# OwlModular.net
KiCad netlist of a schematic drawn in EAGLE
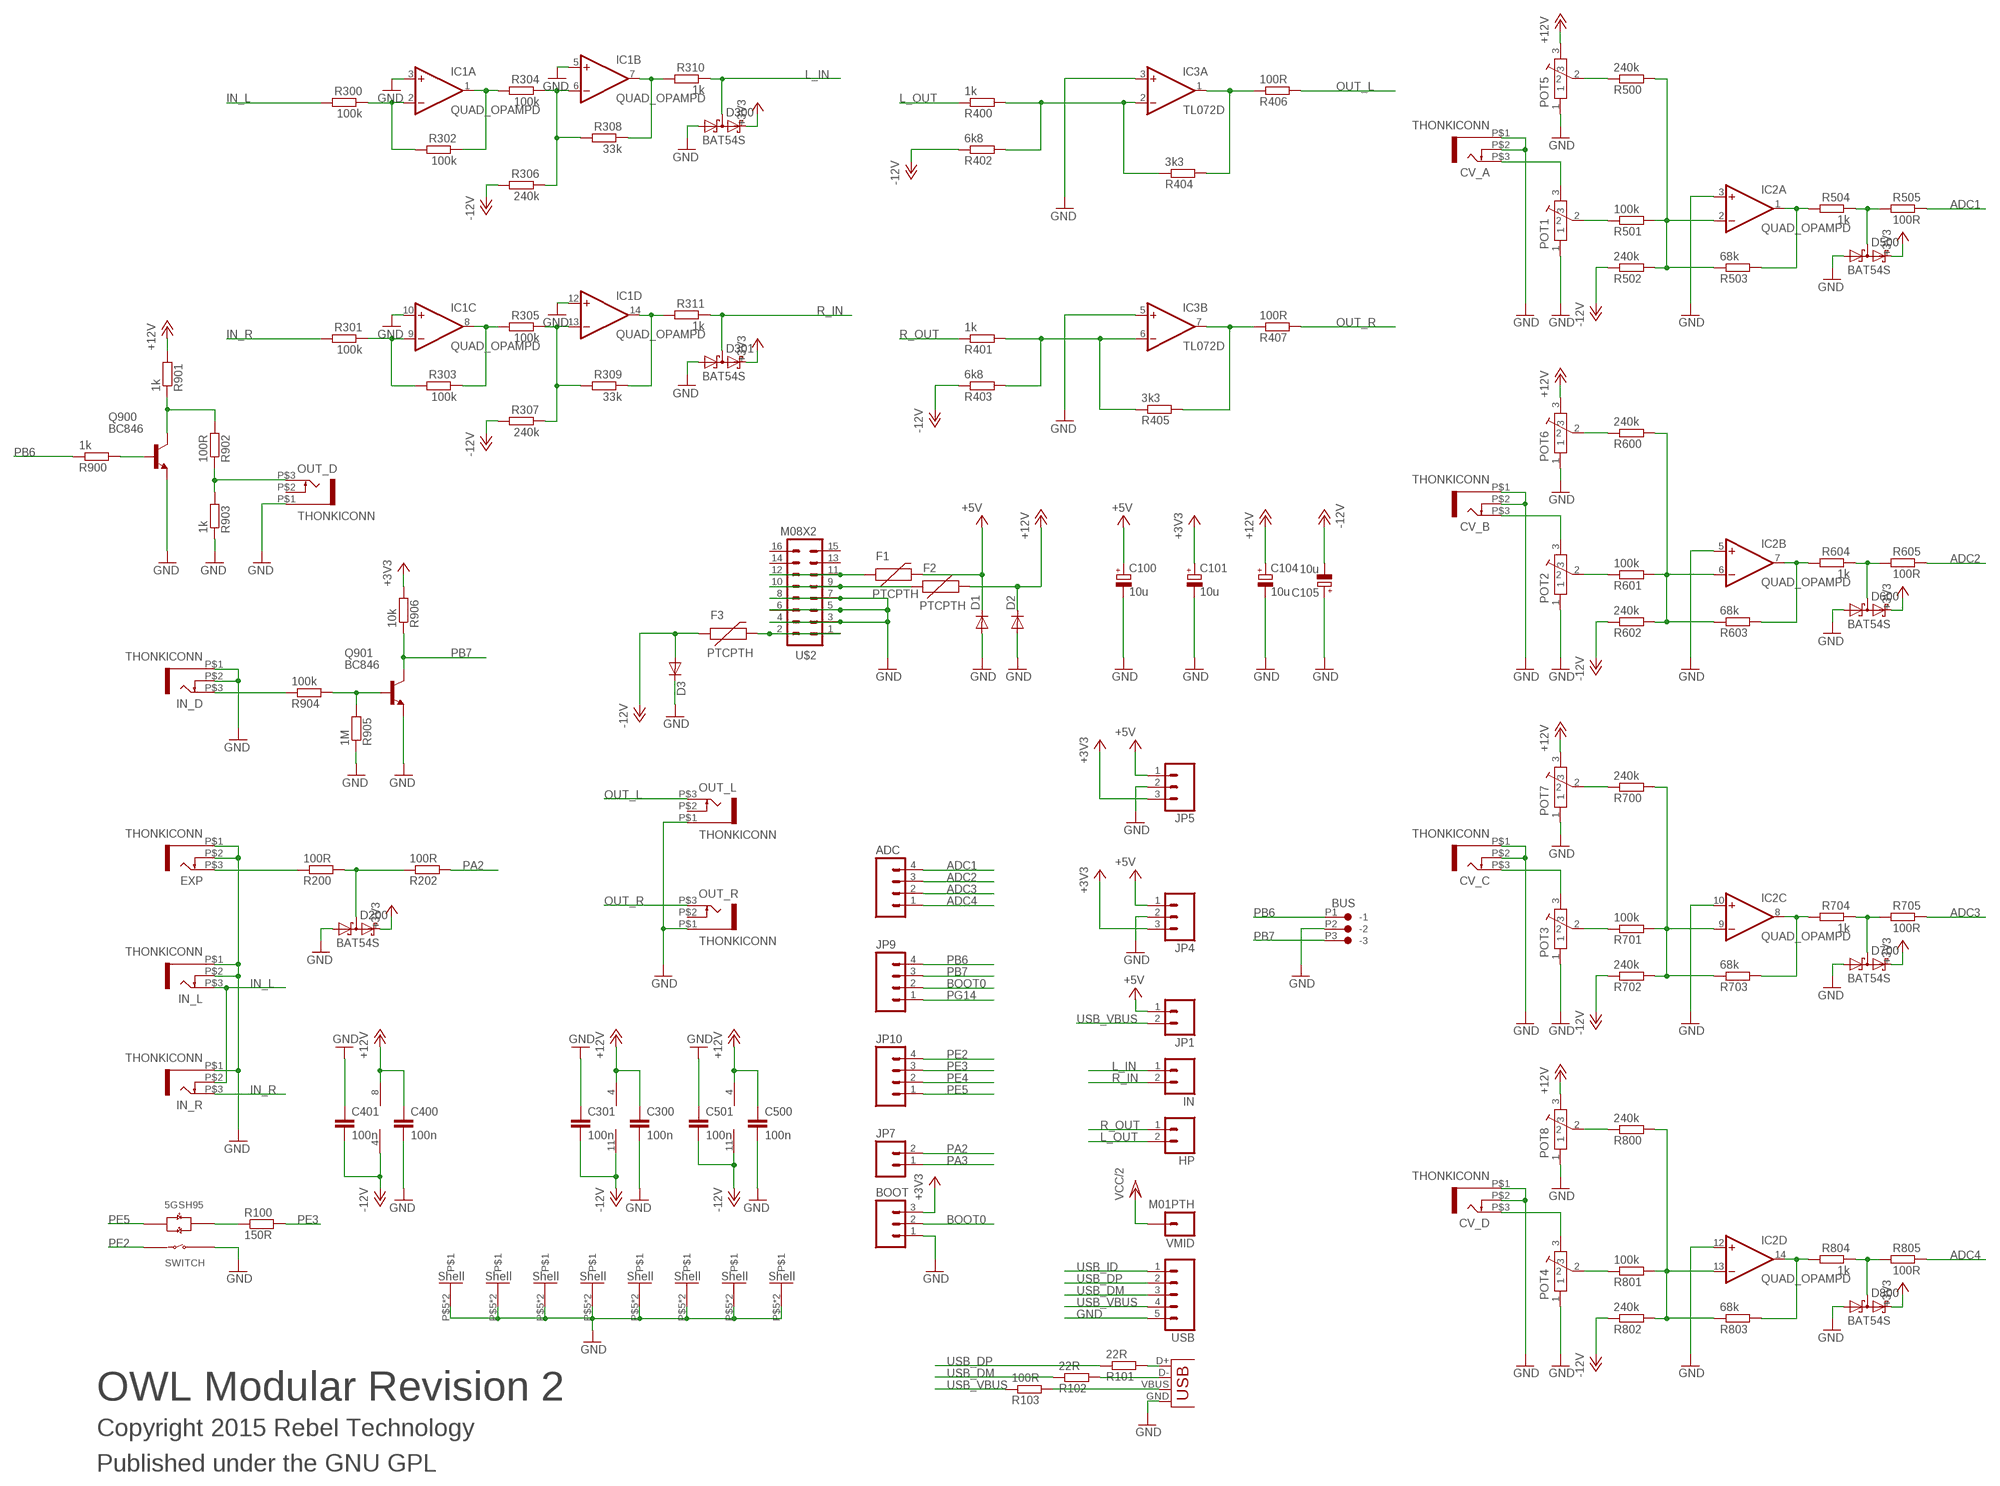
[diagram p0: schematic, sheet 1]

(export (version "E")
  (design (tool "Eeschema 10.0.6"))
  (components
    (comp (ref "ADC")
      (value "M04PTH")
      (footprint "eagle-import:1X04")
      (libsource (lib "eagle-import") (part "M04PTH"))
    )
    (comp (ref "BOOT")
      (value "M03PTH")
      (footprint "eagle-import:1X03")
      (libsource (lib "eagle-import") (part "M03PTH"))
    )
    (comp (ref "BUS")
      (value "CON-JST_PH_3W")
      (footprint "eagle-import:CON-JST_PH_3W")
      (libsource (lib "eagle-import") (part "CON-JST_PH_3W"))
    )
    (comp (ref "C100")
      (value "10u")
      (footprint "eagle-import:PANASONIC_A")
      (libsource (lib "eagle-import") (part "CPOL-EUA"))
    )
    (comp (ref "C101")
      (value "10u")
      (footprint "eagle-import:PANASONIC_A")
      (libsource (lib "eagle-import") (part "CPOL-EUA"))
    )
    (comp (ref "C104")
      (value "10u")
      (footprint "eagle-import:PANASONIC_A")
      (libsource (lib "eagle-import") (part "CPOL-EUA"))
    )
    (comp (ref "C105")
      (value "10u")
      (footprint "eagle-import:PANASONIC_A")
      (libsource (lib "eagle-import") (part "CPOL-EUA"))
    )
    (comp (ref "C300")
      (value "100n")
      (footprint "eagle-import:C0603")
      (libsource (lib "eagle-import") (part "C-EUC0603"))
    )
    (comp (ref "C301")
      (value "100n")
      (footprint "eagle-import:C0603")
      (libsource (lib "eagle-import") (part "C-EUC0603"))
    )
    (comp (ref "C400")
      (value "100n")
      (footprint "eagle-import:C0603")
      (libsource (lib "eagle-import") (part "C-EUC0603"))
    )
    (comp (ref "C401")
      (value "100n")
      (footprint "eagle-import:C0603")
      (libsource (lib "eagle-import") (part "C-EUC0603"))
    )
    (comp (ref "C500")
      (value "100n")
      (footprint "eagle-import:C0603")
      (libsource (lib "eagle-import") (part "C-EUC0603"))
    )
    (comp (ref "C501")
      (value "100n")
      (footprint "eagle-import:C0603")
      (libsource (lib "eagle-import") (part "C-EUC0603"))
    )
    (comp (ref "CV_A")
      (value "THONKICONN")
      (footprint "eagle-import:THONKICONN")
      (libsource (lib "eagle-import") (part "THONKICONN"))
    )
    (comp (ref "CV_B")
      (value "THONKICONN")
      (footprint "eagle-import:THONKICONN")
      (libsource (lib "eagle-import") (part "THONKICONN"))
    )
    (comp (ref "CV_C")
      (value "THONKICONN")
      (footprint "eagle-import:THONKICONN")
      (libsource (lib "eagle-import") (part "THONKICONN"))
    )
    (comp (ref "CV_D")
      (value "THONKICONN")
      (footprint "eagle-import:THONKICONN")
      (libsource (lib "eagle-import") (part "THONKICONN"))
    )
    (comp (ref "D1")
      (value "DIODE1N4001")
      (footprint "eagle-import:DIODE-1N4001")
      (libsource (lib "eagle-import") (part "DIODE1N4001"))
    )
    (comp (ref "D2")
      (value "DIODE1N4001")
      (footprint "eagle-import:DIODE-1N4001")
      (libsource (lib "eagle-import") (part "DIODE1N4001"))
    )
    (comp (ref "D3")
      (value "DIODE1N4001")
      (footprint "eagle-import:DIODE-1N4001")
      (libsource (lib "eagle-import") (part "DIODE1N4001"))
    )
    (comp (ref "D200")
      (value "BAT54S")
      (footprint "eagle-import:SOT23")
      (libsource (lib "eagle-import") (part "BAT54S"))
    )
    (comp (ref "D300")
      (value "BAT54S")
      (footprint "eagle-import:SOT23")
      (libsource (lib "eagle-import") (part "BAT54S"))
    )
    (comp (ref "D301")
      (value "BAT54S")
      (footprint "eagle-import:SOT23")
      (libsource (lib "eagle-import") (part "BAT54S"))
    )
    (comp (ref "D500")
      (value "BAT54S")
      (footprint "eagle-import:SOT23")
      (libsource (lib "eagle-import") (part "BAT54S"))
    )
    (comp (ref "D600")
      (value "BAT54S")
      (footprint "eagle-import:SOT23")
      (libsource (lib "eagle-import") (part "BAT54S"))
    )
    (comp (ref "D700")
      (value "BAT54S")
      (footprint "eagle-import:SOT23")
      (libsource (lib "eagle-import") (part "BAT54S"))
    )
    (comp (ref "D800")
      (value "BAT54S")
      (footprint "eagle-import:SOT23")
      (libsource (lib "eagle-import") (part "BAT54S"))
    )
    (comp (ref "EXP")
      (value "THONKICONN")
      (footprint "eagle-import:THONKICONN")
      (libsource (lib "eagle-import") (part "THONKICONN"))
    )
    (comp (ref "F1")
      (value "PTCPTH")
      (footprint "eagle-import:PTC")
      (libsource (lib "eagle-import") (part "PTCPTH"))
    )
    (comp (ref "F2")
      (value "PTCPTH")
      (footprint "eagle-import:PTC")
      (libsource (lib "eagle-import") (part "PTCPTH"))
    )
    (comp (ref "F3")
      (value "PTCPTH")
      (footprint "eagle-import:PTC")
      (libsource (lib "eagle-import") (part "PTCPTH"))
    )
    (comp (ref "HP")
      (value "M02PTH")
      (footprint "eagle-import:1X02")
      (libsource (lib "eagle-import") (part "M02PTH"))
    )
    (comp (ref "IC1")
      (value "QUAD_OPAMPD")
      (footprint "eagle-import:SO14")
      (libsource (lib "eagle-import") (part "QUAD_OPAMPD"))
    )
    (comp (ref "IC2")
      (value "QUAD_OPAMPD")
      (footprint "eagle-import:SO14")
      (libsource (lib "eagle-import") (part "QUAD_OPAMPD"))
    )
    (comp (ref "IC3")
      (value "TL072D")
      (footprint "eagle-import:SO08")
      (libsource (lib "eagle-import") (part "TL072D"))
    )
    (comp (ref "IN")
      (value "M02PTH")
      (footprint "eagle-import:1X02")
      (libsource (lib "eagle-import") (part "M02PTH"))
    )
    (comp (ref "IN_D")
      (value "THONKICONN")
      (footprint "eagle-import:THONKICONN")
      (libsource (lib "eagle-import") (part "THONKICONN"))
    )
    (comp (ref "IN_L")
      (value "THONKICONN")
      (footprint "eagle-import:THONKICONN")
      (libsource (lib "eagle-import") (part "THONKICONN"))
    )
    (comp (ref "IN_R")
      (value "THONKICONN")
      (footprint "eagle-import:THONKICONN")
      (libsource (lib "eagle-import") (part "THONKICONN"))
    )
    (comp (ref "JP1")
      (value "M02PTH")
      (footprint "eagle-import:1X02")
      (libsource (lib "eagle-import") (part "M02PTH"))
    )
    (comp (ref "JP4")
      (value "M03PTH")
      (footprint "eagle-import:1X03")
      (libsource (lib "eagle-import") (part "M03PTH"))
    )
    (comp (ref "JP5")
      (value "M03PTH")
      (footprint "eagle-import:1X03")
      (libsource (lib "eagle-import") (part "M03PTH"))
    )
    (comp (ref "JP7")
      (value "M02PTH")
      (footprint "eagle-import:1X02")
      (libsource (lib "eagle-import") (part "M02PTH"))
    )
    (comp (ref "JP9")
      (value "M04PTH")
      (footprint "eagle-import:1X04")
      (libsource (lib "eagle-import") (part "M04PTH"))
    )
    (comp (ref "JP10")
      (value "M04PTH")
      (footprint "eagle-import:1X04")
      (libsource (lib "eagle-import") (part "M04PTH"))
    )
    (comp (ref "OUT_D")
      (value "THONKICONN")
      (footprint "eagle-import:THONKICONN")
      (libsource (lib "eagle-import") (part "THONKICONN"))
    )
    (comp (ref "OUT_L")
      (value "THONKICONN")
      (footprint "eagle-import:THONKICONN")
      (libsource (lib "eagle-import") (part "THONKICONN"))
    )
    (comp (ref "OUT_R")
      (value "THONKICONN")
      (footprint "eagle-import:THONKICONN")
      (libsource (lib "eagle-import") (part "THONKICONN"))
    )
    (comp (ref "POT1")
      (value "POT-ALPS-RK09L1140")
      (footprint "eagle-import:POT-ALPS-RK09L1140")
      (libsource (lib "eagle-import") (part "POT-ALPS-RK09L1140"))
    )
    (comp (ref "POT2")
      (value "POT-ALPS-RK09L1140")
      (footprint "eagle-import:POT-ALPS-RK09L1140")
      (libsource (lib "eagle-import") (part "POT-ALPS-RK09L1140"))
    )
    (comp (ref "POT3")
      (value "POT-ALPS-RK09L1140")
      (footprint "eagle-import:POT-ALPS-RK09L1140")
      (libsource (lib "eagle-import") (part "POT-ALPS-RK09L1140"))
    )
    (comp (ref "POT4")
      (value "POT-ALPS-RK09L1140")
      (footprint "eagle-import:POT-ALPS-RK09L1140")
      (libsource (lib "eagle-import") (part "POT-ALPS-RK09L1140"))
    )
    (comp (ref "POT5")
      (value "POT-ALPS-RK09L1140")
      (footprint "eagle-import:POT-ALPS-RK09L1140")
      (libsource (lib "eagle-import") (part "POT-ALPS-RK09L1140"))
    )
    (comp (ref "POT6")
      (value "POT-ALPS-RK09L1140")
      (footprint "eagle-import:POT-ALPS-RK09L1140")
      (libsource (lib "eagle-import") (part "POT-ALPS-RK09L1140"))
    )
    (comp (ref "POT7")
      (value "POT-ALPS-RK09L1140")
      (footprint "eagle-import:POT-ALPS-RK09L1140")
      (libsource (lib "eagle-import") (part "POT-ALPS-RK09L1140"))
    )
    (comp (ref "POT8")
      (value "POT-ALPS-RK09L1140")
      (footprint "eagle-import:POT-ALPS-RK09L1140")
      (libsource (lib "eagle-import") (part "POT-ALPS-RK09L1140"))
    )
    (comp (ref "Q900")
      (value "BC846")
      (footprint "eagle-import:SOT23")
      (libsource (lib "eagle-import") (part "BC846"))
    )
    (comp (ref "Q901")
      (value "BC846")
      (footprint "eagle-import:SOT23")
      (libsource (lib "eagle-import") (part "BC846"))
    )
    (comp (ref "R100")
      (value "150R")
      (footprint "eagle-import:0603")
      (libsource (lib "eagle-import") (part "R-EU_0603"))
    )
    (comp (ref "R101")
      (value "22R")
      (footprint "eagle-import:0603")
      (libsource (lib "eagle-import") (part "R-EU_0603"))
    )
    (comp (ref "R102")
      (value "22R")
      (footprint "eagle-import:0603")
      (libsource (lib "eagle-import") (part "R-EU_0603"))
    )
    (comp (ref "R103")
      (value "100R")
      (footprint "eagle-import:0603")
      (libsource (lib "eagle-import") (part "R-EU_0603"))
    )
    (comp (ref "R200")
      (value "100R")
      (footprint "eagle-import:0603")
      (libsource (lib "eagle-import") (part "R-EU_0603"))
    )
    (comp (ref "R202")
      (value "100R")
      (footprint "eagle-import:0603")
      (libsource (lib "eagle-import") (part "R-EU_0603"))
    )
    (comp (ref "R300")
      (value "100k")
      (footprint "eagle-import:0603")
      (libsource (lib "eagle-import") (part "R-EU_0603"))
    )
    (comp (ref "R301")
      (value "100k")
      (footprint "eagle-import:0603")
      (libsource (lib "eagle-import") (part "R-EU_0603"))
    )
    (comp (ref "R302")
      (value "100k")
      (footprint "eagle-import:0603")
      (libsource (lib "eagle-import") (part "R-EU_0603"))
    )
    (comp (ref "R303")
      (value "100k")
      (footprint "eagle-import:0603")
      (libsource (lib "eagle-import") (part "R-EU_0603"))
    )
    (comp (ref "R304")
      (value "100k")
      (footprint "eagle-import:0603")
      (libsource (lib "eagle-import") (part "R-EU_0603"))
    )
    (comp (ref "R305")
      (value "100k")
      (footprint "eagle-import:0603")
      (libsource (lib "eagle-import") (part "R-EU_0603"))
    )
    (comp (ref "R306")
      (value "240k")
      (footprint "eagle-import:0603")
      (libsource (lib "eagle-import") (part "R-EU_0603"))
    )
    (comp (ref "R307")
      (value "240k")
      (footprint "eagle-import:0603")
      (libsource (lib "eagle-import") (part "R-EU_0603"))
    )
    (comp (ref "R308")
      (value "33k")
      (footprint "eagle-import:0603")
      (libsource (lib "eagle-import") (part "R-EU_0603"))
    )
    (comp (ref "R309")
      (value "33k")
      (footprint "eagle-import:0603")
      (libsource (lib "eagle-import") (part "R-EU_0603"))
    )
    (comp (ref "R310")
      (value "1k")
      (footprint "eagle-import:0603")
      (libsource (lib "eagle-import") (part "R-EU_0603"))
    )
    (comp (ref "R311")
      (value "1k")
      (footprint "eagle-import:0603")
      (libsource (lib "eagle-import") (part "R-EU_0603"))
    )
    (comp (ref "R400")
      (value "1k")
      (footprint "eagle-import:0603")
      (libsource (lib "eagle-import") (part "R-EU_0603"))
    )
    (comp (ref "R401")
      (value "1k")
      (footprint "eagle-import:0603")
      (libsource (lib "eagle-import") (part "R-EU_0603"))
    )
    (comp (ref "R402")
      (value "6k8")
      (footprint "eagle-import:0603")
      (libsource (lib "eagle-import") (part "R-EU_0603"))
    )
    (comp (ref "R403")
      (value "6k8")
      (footprint "eagle-import:0603")
      (libsource (lib "eagle-import") (part "R-EU_0603"))
    )
    (comp (ref "R404")
      (value "3k3")
      (footprint "eagle-import:0603")
      (libsource (lib "eagle-import") (part "R-EU_0603"))
    )
    (comp (ref "R405")
      (value "3k3")
      (footprint "eagle-import:0603")
      (libsource (lib "eagle-import") (part "R-EU_0603"))
    )
    (comp (ref "R406")
      (value "100R")
      (footprint "eagle-import:0603")
      (libsource (lib "eagle-import") (part "R-EU_0603"))
    )
    (comp (ref "R407")
      (value "100R")
      (footprint "eagle-import:0603")
      (libsource (lib "eagle-import") (part "R-EU_0603"))
    )
    (comp (ref "R500")
      (value "240k")
      (footprint "eagle-import:0603")
      (libsource (lib "eagle-import") (part "R-EU_0603"))
    )
    (comp (ref "R501")
      (value "100k")
      (footprint "eagle-import:0603")
      (libsource (lib "eagle-import") (part "R-EU_0603"))
    )
    (comp (ref "R502")
      (value "240k")
      (footprint "eagle-import:0603")
      (libsource (lib "eagle-import") (part "R-EU_0603"))
    )
    (comp (ref "R503")
      (value "68k")
      (footprint "eagle-import:0603")
      (libsource (lib "eagle-import") (part "R-EU_0603"))
    )
    (comp (ref "R504")
      (value "1k")
      (footprint "eagle-import:0603")
      (libsource (lib "eagle-import") (part "R-EU_0603"))
    )
    (comp (ref "R505")
      (value "100R")
      (footprint "eagle-import:0603")
      (libsource (lib "eagle-import") (part "R-EU_0603"))
    )
    (comp (ref "R600")
      (value "240k")
      (footprint "eagle-import:0603")
      (libsource (lib "eagle-import") (part "R-EU_0603"))
    )
    (comp (ref "R601")
      (value "100k")
      (footprint "eagle-import:0603")
      (libsource (lib "eagle-import") (part "R-EU_0603"))
    )
    (comp (ref "R602")
      (value "240k")
      (footprint "eagle-import:0603")
      (libsource (lib "eagle-import") (part "R-EU_0603"))
    )
    (comp (ref "R603")
      (value "68k")
      (footprint "eagle-import:0603")
      (libsource (lib "eagle-import") (part "R-EU_0603"))
    )
    (comp (ref "R604")
      (value "1k")
      (footprint "eagle-import:0603")
      (libsource (lib "eagle-import") (part "R-EU_0603"))
    )
    (comp (ref "R605")
      (value "100R")
      (footprint "eagle-import:0603")
      (libsource (lib "eagle-import") (part "R-EU_0603"))
    )
    (comp (ref "R700")
      (value "240k")
      (footprint "eagle-import:0603")
      (libsource (lib "eagle-import") (part "R-EU_0603"))
    )
    (comp (ref "R701")
      (value "100k")
      (footprint "eagle-import:0603")
      (libsource (lib "eagle-import") (part "R-EU_0603"))
    )
    (comp (ref "R702")
      (value "240k")
      (footprint "eagle-import:0603")
      (libsource (lib "eagle-import") (part "R-EU_0603"))
    )
    (comp (ref "R703")
      (value "68k")
      (footprint "eagle-import:0603")
      (libsource (lib "eagle-import") (part "R-EU_0603"))
    )
    (comp (ref "R704")
      (value "1k")
      (footprint "eagle-import:0603")
      (libsource (lib "eagle-import") (part "R-EU_0603"))
    )
    (comp (ref "R705")
      (value "100R")
      (footprint "eagle-import:0603")
      (libsource (lib "eagle-import") (part "R-EU_0603"))
    )
    (comp (ref "R800")
      (value "240k")
      (footprint "eagle-import:0603")
      (libsource (lib "eagle-import") (part "R-EU_0603"))
    )
    (comp (ref "R801")
      (value "100k")
      (footprint "eagle-import:0603")
      (libsource (lib "eagle-import") (part "R-EU_0603"))
    )
    (comp (ref "R802")
      (value "240k")
      (footprint "eagle-import:0603")
      (libsource (lib "eagle-import") (part "R-EU_0603"))
    )
    (comp (ref "R803")
      (value "68k")
      (footprint "eagle-import:0603")
      (libsource (lib "eagle-import") (part "R-EU_0603"))
    )
    (comp (ref "R804")
      (value "1k")
      (footprint "eagle-import:0603")
      (libsource (lib "eagle-import") (part "R-EU_0603"))
    )
    (comp (ref "R805")
      (value "100R")
      (footprint "eagle-import:0603")
      (libsource (lib "eagle-import") (part "R-EU_0603"))
    )
    (comp (ref "R900")
      (value "1k")
      (footprint "eagle-import:0603")
      (libsource (lib "eagle-import") (part "R-EU_0603"))
    )
    (comp (ref "R901")
      (value "1k")
      (footprint "eagle-import:0603")
      (libsource (lib "eagle-import") (part "R-EU_0603"))
    )
    (comp (ref "R902")
      (value "100R")
      (footprint "eagle-import:0603")
      (libsource (lib "eagle-import") (part "R-EU_0603"))
    )
    (comp (ref "R903")
      (value "1k")
      (footprint "eagle-import:0603")
      (libsource (lib "eagle-import") (part "R-EU_0603"))
    )
    (comp (ref "R904")
      (value "100k")
      (footprint "eagle-import:0603")
      (libsource (lib "eagle-import") (part "R-EU_0603"))
    )
    (comp (ref "R905")
      (value "1M")
      (footprint "eagle-import:0603")
      (libsource (lib "eagle-import") (part "R-EU_0603"))
    )
    (comp (ref "R906")
      (value "10k")
      (footprint "eagle-import:0603")
      (libsource (lib "eagle-import") (part "R-EU_0603"))
    )
    (comp (ref "U$1")
      (value "5GTH9")
      (footprint "eagle-import:5GTH9")
      (libsource (lib "eagle-import") (part "5GTH9"))
    )
    (comp (ref "U$2")
      (value "M08X2")
      (footprint "eagle-import:2X8")
      (libsource (lib "eagle-import") (part "M08X2"))
    )
    (comp (ref "USB")
      (value "M05PTH")
      (footprint "eagle-import:1X05")
      (libsource (lib "eagle-import") (part "M05PTH"))
    )
    (comp (ref "VMID")
      (value "M01PTH")
      (footprint "eagle-import:1X01")
      (libsource (lib "eagle-import") (part "M01PTH"))
    )
    (comp (ref "X1")
      (value "USBPTH-VERTICAL")
      (footprint "eagle-import:USB-B-PTH-VERTICAL")
      (libsource (lib "eagle-import") (part "USBPTH-VERTICAL"))
    )
  )
  (nets
    (net (code "1") (name "+3V3") (class "Default")
      (node (ref "BOOT") (pin "3") (pinfunction "3_3") (pintype "passive"))
      (node (ref "C101") (pin "+") (pinfunction "+_+") (pintype "passive"))
      (node (ref "D200") (pin "2") (pinfunction "C2_2") (pintype "passive"))
      (node (ref "D300") (pin "2") (pinfunction "C2_2") (pintype "passive"))
      (node (ref "D301") (pin "2") (pinfunction "C2_2") (pintype "passive"))
      (node (ref "D500") (pin "2") (pinfunction "C2_2") (pintype "passive"))
      (node (ref "D600") (pin "2") (pinfunction "C2_2") (pintype "passive"))
      (node (ref "D700") (pin "2") (pinfunction "C2_2") (pintype "passive"))
      (node (ref "D800") (pin "2") (pinfunction "C2_2") (pintype "passive"))
      (node (ref "JP4") (pin "3") (pinfunction "3_3") (pintype "passive"))
      (node (ref "JP5") (pin "3") (pinfunction "3_3") (pintype "passive"))
      (node (ref "R906") (pin "2") (pinfunction "2_2") (pintype "passive"))
    )
    (net (code "2") (name "+5V") (class "Default")
      (node (ref "C100") (pin "+") (pinfunction "+_+") (pintype "passive"))
      (node (ref "D1") (pin "C") (pinfunction "C_C") (pintype "passive"))
      (node (ref "F1") (pin "P$2") (pinfunction "2_P$2") (pintype "bidirectional"))
      (node (ref "JP1") (pin "1") (pinfunction "1_1") (pintype "passive"))
      (node (ref "JP4") (pin "1") (pinfunction "1_1") (pintype "passive"))
      (node (ref "JP5") (pin "1") (pinfunction "1_1") (pintype "passive"))
    )
    (net (code "3") (name "+12V") (class "Default")
      (node (ref "C104") (pin "+") (pinfunction "+_+") (pintype "passive"))
      (node (ref "C300") (pin "1") (pinfunction "1_1") (pintype "passive"))
      (node (ref "C400") (pin "1") (pinfunction "1_1") (pintype "passive"))
      (node (ref "C500") (pin "1") (pinfunction "1_1") (pintype "passive"))
      (node (ref "D2") (pin "C") (pinfunction "C_C") (pintype "passive"))
      (node (ref "F2") (pin "P$2") (pinfunction "2_P$2") (pintype "bidirectional"))
      (node (ref "IC1") (pin "4") (pinfunction "V+_4") (pintype "power_in"))
      (node (ref "IC2") (pin "4") (pinfunction "V+_4") (pintype "power_in"))
      (node (ref "IC3") (pin "8") (pinfunction "V+_8") (pintype "power_in"))
      (node (ref "POT5") (pin "3") (pinfunction "3_3") (pintype "bidirectional"))
      (node (ref "POT6") (pin "3") (pinfunction "3_3") (pintype "bidirectional"))
      (node (ref "POT7") (pin "3") (pinfunction "3_3") (pintype "bidirectional"))
      (node (ref "POT8") (pin "3") (pinfunction "3_3") (pintype "bidirectional"))
      (node (ref "R901") (pin "2") (pinfunction "2_2") (pintype "passive"))
    )
    (net (code "4") (name "-12V") (class "Default")
      (node (ref "C105") (pin "-") (pinfunction "-_-") (pintype "passive"))
      (node (ref "C301") (pin "2") (pinfunction "2_2") (pintype "passive"))
      (node (ref "C401") (pin "2") (pinfunction "2_2") (pintype "passive"))
      (node (ref "C501") (pin "2") (pinfunction "2_2") (pintype "passive"))
      (node (ref "D3") (pin "A") (pinfunction "A_A") (pintype "passive"))
      (node (ref "F3") (pin "P$1") (pinfunction "1_P$1") (pintype "bidirectional"))
      (node (ref "IC1") (pin "11") (pinfunction "V-_11") (pintype "power_in"))
      (node (ref "IC2") (pin "11") (pinfunction "V-_11") (pintype "power_in"))
      (node (ref "IC3") (pin "4") (pinfunction "V-_4") (pintype "power_in"))
      (node (ref "R306") (pin "2") (pinfunction "2_2") (pintype "passive"))
      (node (ref "R307") (pin "2") (pinfunction "2_2") (pintype "passive"))
      (node (ref "R402") (pin "1") (pinfunction "1_1") (pintype "passive"))
      (node (ref "R403") (pin "1") (pinfunction "1_1") (pintype "passive"))
      (node (ref "R502") (pin "1") (pinfunction "1_1") (pintype "passive"))
      (node (ref "R602") (pin "1") (pinfunction "1_1") (pintype "passive"))
      (node (ref "R702") (pin "1") (pinfunction "1_1") (pintype "passive"))
      (node (ref "R802") (pin "1") (pinfunction "1_1") (pintype "passive"))
    )
    (net (code "5") (name "/ADC1") (class "Default")
      (node (ref "ADC") (pin "4") (pinfunction "4_4") (pintype "passive"))
      (node (ref "R505") (pin "1") (pinfunction "1_1") (pintype "passive"))
    )
    (net (code "6") (name "/ADC2") (class "Default")
      (node (ref "ADC") (pin "3") (pinfunction "3_3") (pintype "passive"))
      (node (ref "R605") (pin "1") (pinfunction "1_1") (pintype "passive"))
    )
    (net (code "7") (name "/ADC3") (class "Default")
      (node (ref "ADC") (pin "2") (pinfunction "2_2") (pintype "passive"))
      (node (ref "R705") (pin "1") (pinfunction "1_1") (pintype "passive"))
    )
    (net (code "8") (name "/ADC4") (class "Default")
      (node (ref "ADC") (pin "1") (pinfunction "1_1") (pintype "passive"))
      (node (ref "R805") (pin "1") (pinfunction "1_1") (pintype "passive"))
    )
    (net (code "9") (name "/BOOT0") (class "Default")
      (node (ref "BOOT") (pin "2") (pinfunction "2_2") (pintype "passive"))
      (node (ref "JP9") (pin "2") (pinfunction "2_2") (pintype "passive"))
    )
    (net (code "10") (name "/IN_L") (class "Default")
      (node (ref "IN_L") (pin "P$3") (pinfunction "3_P$3") (pintype "passive"))
      (node (ref "IN_R") (pin "P$2") (pinfunction "4_P$2") (pintype "passive"))
      (node (ref "R300") (pin "2") (pinfunction "2_2") (pintype "passive"))
    )
    (net (code "11") (name "/IN_R") (class "Default")
      (node (ref "IN_R") (pin "P$3") (pinfunction "3_P$3") (pintype "passive"))
      (node (ref "R301") (pin "2") (pinfunction "2_2") (pintype "passive"))
    )
    (net (code "12") (name "/L_IN") (class "Default")
      (node (ref "D300") (pin "3") (pinfunction "C1A2_3") (pintype "passive"))
      (node (ref "IN") (pin "1") (pinfunction "1_1") (pintype "passive"))
      (node (ref "R310") (pin "1") (pinfunction "1_1") (pintype "passive"))
    )
    (net (code "13") (name "/L_OUT") (class "Default")
      (node (ref "HP") (pin "2") (pinfunction "2_2") (pintype "passive"))
      (node (ref "R400") (pin "1") (pinfunction "1_1") (pintype "passive"))
    )
    (net (code "14") (name "/OUT_L") (class "Default")
      (node (ref "OUT_L") (pin "P$3") (pinfunction "3_P$3") (pintype "passive"))
      (node (ref "R406") (pin "2") (pinfunction "2_2") (pintype "passive"))
    )
    (net (code "15") (name "/OUT_R") (class "Default")
      (node (ref "OUT_R") (pin "P$3") (pinfunction "3_P$3") (pintype "passive"))
      (node (ref "R407") (pin "2") (pinfunction "2_2") (pintype "passive"))
    )
    (net (code "16") (name "/PA2") (class "Default")
      (node (ref "JP7") (pin "2") (pinfunction "2_2") (pintype "passive"))
      (node (ref "R202") (pin "2") (pinfunction "2_2") (pintype "passive"))
    )
    (net (code "17") (name "/PA3") (class "Default")
      (node (ref "JP7") (pin "1") (pinfunction "1_1") (pintype "passive"))
    )
    (net (code "18") (name "/PB6") (class "Default")
      (node (ref "BUS") (pin "P1") (pinfunction "-1_P1") (pintype "bidirectional"))
      (node (ref "JP9") (pin "4") (pinfunction "4_4") (pintype "passive"))
      (node (ref "R900") (pin "1") (pinfunction "1_1") (pintype "passive"))
    )
    (net (code "19") (name "/PB7") (class "Default")
      (node (ref "BUS") (pin "P3") (pinfunction "-3_P3") (pintype "bidirectional"))
      (node (ref "JP9") (pin "3") (pinfunction "3_3") (pintype "passive"))
      (node (ref "Q901") (pin "3") (pinfunction "C_3") (pintype "passive"))
      (node (ref "R906") (pin "1") (pinfunction "1_1") (pintype "passive"))
    )
    (net (code "20") (name "/PE2") (class "Default")
      (node (ref "JP10") (pin "4") (pinfunction "4_4") (pintype "passive"))
      (node (ref "U$1") (pin "4") (pinfunction "SWITCH_A_4") (pintype "power_in"))
    )
    (net (code "21") (name "/PE3") (class "Default")
      (node (ref "JP10") (pin "3") (pinfunction "3_3") (pintype "passive"))
      (node (ref "R100") (pin "2") (pinfunction "2_2") (pintype "passive"))
    )
    (net (code "22") (name "/PE4") (class "Default")
      (node (ref "JP10") (pin "2") (pinfunction "2_2") (pintype "passive"))
    )
    (net (code "23") (name "/PE5") (class "Default")
      (node (ref "JP10") (pin "1") (pinfunction "1_1") (pintype "passive"))
      (node (ref "U$1") (pin "-2") (pinfunction "LED_G+_-2") (pintype "input"))
    )
    (net (code "24") (name "/PG14") (class "Default")
      (node (ref "JP9") (pin "1") (pinfunction "1_1") (pintype "passive"))
    )
    (net (code "25") (name "/R_IN") (class "Default")
      (node (ref "D301") (pin "3") (pinfunction "C1A2_3") (pintype "passive"))
      (node (ref "IN") (pin "2") (pinfunction "2_2") (pintype "passive"))
      (node (ref "R311") (pin "1") (pinfunction "1_1") (pintype "passive"))
    )
    (net (code "26") (name "/R_OUT") (class "Default")
      (node (ref "HP") (pin "1") (pinfunction "1_1") (pintype "passive"))
      (node (ref "R401") (pin "1") (pinfunction "1_1") (pintype "passive"))
    )
    (net (code "27") (name "/USB_DM") (class "Default")
      (node (ref "R102") (pin "1") (pinfunction "1_1") (pintype "passive"))
      (node (ref "USB") (pin "3") (pinfunction "3_3") (pintype "passive"))
    )
    (net (code "28") (name "/USB_DP") (class "Default")
      (node (ref "R101") (pin "1") (pinfunction "1_1") (pintype "passive"))
      (node (ref "USB") (pin "2") (pinfunction "2_2") (pintype "passive"))
    )
    (net (code "29") (name "/USB_ID") (class "Default")
      (node (ref "USB") (pin "1") (pinfunction "1_1") (pintype "passive"))
    )
    (net (code "30") (name "/USB_VBUS") (class "Default")
      (node (ref "JP1") (pin "2") (pinfunction "2_2") (pintype "passive"))
      (node (ref "R103") (pin "1") (pinfunction "1_1") (pintype "passive"))
      (node (ref "USB") (pin "4") (pinfunction "4_4") (pintype "passive"))
    )
    (net (code "31") (name "GND") (class "Default")
      (node (ref "BOOT") (pin "1") (pinfunction "1_1") (pintype "passive"))
      (node (ref "BUS") (pin "P2") (pinfunction "-2_P2") (pintype "bidirectional"))
      (node (ref "C100") (pin "-") (pinfunction "-_-") (pintype "passive"))
      (node (ref "C101") (pin "-") (pinfunction "-_-") (pintype "passive"))
      (node (ref "C104") (pin "-") (pinfunction "-_-") (pintype "passive"))
      (node (ref "C105") (pin "+") (pinfunction "+_+") (pintype "passive"))
      (node (ref "C300") (pin "2") (pinfunction "2_2") (pintype "passive"))
      (node (ref "C301") (pin "1") (pinfunction "1_1") (pintype "passive"))
      (node (ref "C400") (pin "2") (pinfunction "2_2") (pintype "passive"))
      (node (ref "C401") (pin "1") (pinfunction "1_1") (pintype "passive"))
      (node (ref "C500") (pin "2") (pinfunction "2_2") (pintype "passive"))
      (node (ref "C501") (pin "1") (pinfunction "1_1") (pintype "passive"))
      (node (ref "CV_A") (pin "P$1") (pinfunction "5_P$1") (pintype "passive"))
      (node (ref "CV_A") (pin "P$2") (pinfunction "4_P$2") (pintype "passive"))
      (node (ref "CV_B") (pin "P$1") (pinfunction "5_P$1") (pintype "passive"))
      (node (ref "CV_B") (pin "P$2") (pinfunction "4_P$2") (pintype "passive"))
      (node (ref "CV_C") (pin "P$1") (pinfunction "5_P$1") (pintype "passive"))
      (node (ref "CV_C") (pin "P$2") (pinfunction "4_P$2") (pintype "passive"))
      (node (ref "CV_D") (pin "P$1") (pinfunction "5_P$1") (pintype "passive"))
      (node (ref "CV_D") (pin "P$2") (pinfunction "4_P$2") (pintype "passive"))
      (node (ref "D1") (pin "A") (pinfunction "A_A") (pintype "passive"))
      (node (ref "D2") (pin "A") (pinfunction "A_A") (pintype "passive"))
      (node (ref "D200") (pin "1") (pinfunction "A1_1") (pintype "passive"))
      (node (ref "D3") (pin "C") (pinfunction "C_C") (pintype "passive"))
      (node (ref "D300") (pin "1") (pinfunction "A1_1") (pintype "passive"))
      (node (ref "D301") (pin "1") (pinfunction "A1_1") (pintype "passive"))
      (node (ref "D500") (pin "1") (pinfunction "A1_1") (pintype "passive"))
      (node (ref "D600") (pin "1") (pinfunction "A1_1") (pintype "passive"))
      (node (ref "D700") (pin "1") (pinfunction "A1_1") (pintype "passive"))
      (node (ref "D800") (pin "1") (pinfunction "A1_1") (pintype "passive"))
      (node (ref "EXP") (pin "P$1") (pinfunction "5_P$1") (pintype "passive"))
      (node (ref "EXP") (pin "P$2") (pinfunction "4_P$2") (pintype "passive"))
      (node (ref "IC1") (pin "10") (pinfunction "+IN_10") (pintype "input"))
      (node (ref "IC1") (pin "12") (pinfunction "+IN_12") (pintype "input"))
      (node (ref "IC1") (pin "3") (pinfunction "+IN_3") (pintype "input"))
      (node (ref "IC1") (pin "5") (pinfunction "+IN_5") (pintype "input"))
      (node (ref "IC2") (pin "10") (pinfunction "+IN_10") (pintype "input"))
      (node (ref "IC2") (pin "12") (pinfunction "+IN_12") (pintype "input"))
      (node (ref "IC2") (pin "3") (pinfunction "+IN_3") (pintype "input"))
      (node (ref "IC2") (pin "5") (pinfunction "+IN_5") (pintype "input"))
      (node (ref "IC3") (pin "3") (pinfunction "+IN_3") (pintype "input"))
      (node (ref "IC3") (pin "5") (pinfunction "+IN_5") (pintype "input"))
      (node (ref "IN_D") (pin "P$1") (pinfunction "5_P$1") (pintype "passive"))
      (node (ref "IN_D") (pin "P$2") (pinfunction "4_P$2") (pintype "passive"))
      (node (ref "IN_L") (pin "P$1") (pinfunction "5_P$1") (pintype "passive"))
      (node (ref "IN_L") (pin "P$2") (pinfunction "4_P$2") (pintype "passive"))
      (node (ref "IN_R") (pin "P$1") (pinfunction "5_P$1") (pintype "passive"))
      (node (ref "JP4") (pin "2") (pinfunction "2_2") (pintype "passive"))
      (node (ref "JP5") (pin "2") (pinfunction "2_2") (pintype "passive"))
      (node (ref "OUT_D") (pin "P$1") (pinfunction "5_P$1") (pintype "passive"))
      (node (ref "OUT_L") (pin "P$1") (pinfunction "5_P$1") (pintype "passive"))
      (node (ref "OUT_R") (pin "P$1") (pinfunction "5_P$1") (pintype "passive"))
      (node (ref "POT1") (pin "1") (pinfunction "1_1") (pintype "bidirectional"))
      (node (ref "POT1") (pin "P$5") (pinfunction "P$1_P$5") (pintype "bidirectional"))
      (node (ref "POT1") (pin "P$6") (pinfunction "P$1_P$6") (pintype "bidirectional"))
      (node (ref "POT2") (pin "1") (pinfunction "1_1") (pintype "bidirectional"))
      (node (ref "POT2") (pin "P$5") (pinfunction "P$1_P$5") (pintype "bidirectional"))
      (node (ref "POT2") (pin "P$6") (pinfunction "P$1_P$6") (pintype "bidirectional"))
      (node (ref "POT3") (pin "1") (pinfunction "1_1") (pintype "bidirectional"))
      (node (ref "POT3") (pin "P$5") (pinfunction "P$1_P$5") (pintype "bidirectional"))
      (node (ref "POT3") (pin "P$6") (pinfunction "P$1_P$6") (pintype "bidirectional"))
      (node (ref "POT4") (pin "1") (pinfunction "1_1") (pintype "bidirectional"))
      (node (ref "POT4") (pin "P$5") (pinfunction "P$1_P$5") (pintype "bidirectional"))
      (node (ref "POT4") (pin "P$6") (pinfunction "P$1_P$6") (pintype "bidirectional"))
      (node (ref "POT5") (pin "1") (pinfunction "1_1") (pintype "bidirectional"))
      (node (ref "POT5") (pin "P$5") (pinfunction "P$1_P$5") (pintype "bidirectional"))
      (node (ref "POT5") (pin "P$6") (pinfunction "P$1_P$6") (pintype "bidirectional"))
      (node (ref "POT6") (pin "1") (pinfunction "1_1") (pintype "bidirectional"))
      (node (ref "POT6") (pin "P$5") (pinfunction "P$1_P$5") (pintype "bidirectional"))
      (node (ref "POT6") (pin "P$6") (pinfunction "P$1_P$6") (pintype "bidirectional"))
      (node (ref "POT7") (pin "1") (pinfunction "1_1") (pintype "bidirectional"))
      (node (ref "POT7") (pin "P$5") (pinfunction "P$1_P$5") (pintype "bidirectional"))
      (node (ref "POT7") (pin "P$6") (pinfunction "P$1_P$6") (pintype "bidirectional"))
      (node (ref "POT8") (pin "1") (pinfunction "1_1") (pintype "bidirectional"))
      (node (ref "POT8") (pin "P$5") (pinfunction "P$1_P$5") (pintype "bidirectional"))
      (node (ref "POT8") (pin "P$6") (pinfunction "P$1_P$6") (pintype "bidirectional"))
      (node (ref "Q900") (pin "2") (pinfunction "E_2") (pintype "passive"))
      (node (ref "Q901") (pin "2") (pinfunction "E_2") (pintype "passive"))
      (node (ref "R903") (pin "1") (pinfunction "1_1") (pintype "passive"))
      (node (ref "R905") (pin "1") (pinfunction "1_1") (pintype "passive"))
      (node (ref "U$1") (pin "1") (pinfunction "SWITCH_B_1") (pintype "power_in"))
      (node (ref "U$2") (pin "3") (pinfunction "3_3") (pintype "passive"))
      (node (ref "U$2") (pin "4") (pinfunction "4_4") (pintype "passive"))
      (node (ref "U$2") (pin "5") (pinfunction "5_5") (pintype "passive"))
      (node (ref "U$2") (pin "6") (pinfunction "6_6") (pintype "passive"))
      (node (ref "U$2") (pin "7") (pinfunction "7_7") (pintype "passive"))
      (node (ref "U$2") (pin "8") (pinfunction "8_8") (pintype "passive"))
      (node (ref "USB") (pin "5") (pinfunction "5_5") (pintype "passive"))
      (node (ref "X1") (pin "GND") (pinfunction "GND_GND") (pintype "bidirectional"))
    )
    (net (code "32") (name "Net-(CV_A-3)") (class "Default")
      (node (ref "CV_A") (pin "P$3") (pinfunction "3_P$3") (pintype "passive"))
      (node (ref "POT1") (pin "3") (pinfunction "3_3") (pintype "bidirectional"))
    )
    (net (code "33") (name "Net-(CV_B-3)") (class "Default")
      (node (ref "CV_B") (pin "P$3") (pinfunction "3_P$3") (pintype "passive"))
      (node (ref "POT2") (pin "3") (pinfunction "3_3") (pintype "bidirectional"))
    )
    (net (code "34") (name "Net-(CV_C-3)") (class "Default")
      (node (ref "CV_C") (pin "P$3") (pinfunction "3_P$3") (pintype "passive"))
      (node (ref "POT3") (pin "3") (pinfunction "3_3") (pintype "bidirectional"))
    )
    (net (code "35") (name "Net-(CV_D-3)") (class "Default")
      (node (ref "CV_D") (pin "P$3") (pinfunction "3_P$3") (pintype "passive"))
      (node (ref "POT4") (pin "3") (pinfunction "3_3") (pintype "bidirectional"))
    )
    (net (code "36") (name "Net-(D200-C1A2)") (class "Default")
      (node (ref "D200") (pin "3") (pinfunction "C1A2_3") (pintype "passive"))
      (node (ref "R200") (pin "2") (pinfunction "2_2") (pintype "passive"))
      (node (ref "R202") (pin "1") (pinfunction "1_1") (pintype "passive"))
    )
    (net (code "37") (name "Net-(D500-C1A2)") (class "Default")
      (node (ref "D500") (pin "3") (pinfunction "C1A2_3") (pintype "passive"))
      (node (ref "R504") (pin "1") (pinfunction "1_1") (pintype "passive"))
      (node (ref "R505") (pin "2") (pinfunction "2_2") (pintype "passive"))
    )
    (net (code "38") (name "Net-(D600-C1A2)") (class "Default")
      (node (ref "D600") (pin "3") (pinfunction "C1A2_3") (pintype "passive"))
      (node (ref "R604") (pin "1") (pinfunction "1_1") (pintype "passive"))
      (node (ref "R605") (pin "2") (pinfunction "2_2") (pintype "passive"))
    )
    (net (code "39") (name "Net-(D700-C1A2)") (class "Default")
      (node (ref "D700") (pin "3") (pinfunction "C1A2_3") (pintype "passive"))
      (node (ref "R704") (pin "1") (pinfunction "1_1") (pintype "passive"))
      (node (ref "R705") (pin "2") (pinfunction "2_2") (pintype "passive"))
    )
    (net (code "40") (name "Net-(D800-C1A2)") (class "Default")
      (node (ref "D800") (pin "3") (pinfunction "C1A2_3") (pintype "passive"))
      (node (ref "R804") (pin "1") (pinfunction "1_1") (pintype "passive"))
      (node (ref "R805") (pin "2") (pinfunction "2_2") (pintype "passive"))
    )
    (net (code "41") (name "Net-(EXP-3)") (class "Default")
      (node (ref "EXP") (pin "P$3") (pinfunction "3_P$3") (pintype "passive"))
      (node (ref "R200") (pin "1") (pinfunction "1_1") (pintype "passive"))
    )
    (net (code "42") (name "Net-(F1-1)") (class "Default")
      (node (ref "F1") (pin "P$1") (pinfunction "1_P$1") (pintype "bidirectional"))
      (node (ref "U$2") (pin "11") (pinfunction "11_11") (pintype "passive"))
      (node (ref "U$2") (pin "12") (pinfunction "12_12") (pintype "passive"))
    )
    (net (code "43") (name "Net-(F2-1)") (class "Default")
      (node (ref "F2") (pin "P$1") (pinfunction "1_P$1") (pintype "bidirectional"))
      (node (ref "U$2") (pin "10") (pinfunction "10_10") (pintype "passive"))
      (node (ref "U$2") (pin "9") (pinfunction "9_9") (pintype "passive"))
    )
    (net (code "44") (name "Net-(F3-2)") (class "Default")
      (node (ref "F3") (pin "P$2") (pinfunction "2_P$2") (pintype "bidirectional"))
      (node (ref "U$2") (pin "1") (pinfunction "1_1") (pintype "passive"))
      (node (ref "U$2") (pin "2") (pinfunction "2_2") (pintype "passive"))
    )
    (net (code "45") (name "Net-(IC1A--IN)") (class "Default")
      (node (ref "IC1") (pin "2") (pinfunction "-IN_2") (pintype "input"))
      (node (ref "R300") (pin "1") (pinfunction "1_1") (pintype "passive"))
      (node (ref "R302") (pin "2") (pinfunction "2_2") (pintype "passive"))
    )
    (net (code "46") (name "Net-(IC1A-OUT)") (class "Default")
      (node (ref "IC1") (pin "1") (pinfunction "OUT_1") (pintype "output"))
      (node (ref "R302") (pin "1") (pinfunction "1_1") (pintype "passive"))
      (node (ref "R304") (pin "2") (pinfunction "2_2") (pintype "passive"))
    )
    (net (code "47") (name "Net-(IC1B--IN)") (class "Default")
      (node (ref "IC1") (pin "6") (pinfunction "-IN_6") (pintype "input"))
      (node (ref "R304") (pin "1") (pinfunction "1_1") (pintype "passive"))
      (node (ref "R306") (pin "1") (pinfunction "1_1") (pintype "passive"))
      (node (ref "R308") (pin "2") (pinfunction "2_2") (pintype "passive"))
    )
    (net (code "48") (name "Net-(IC1B-OUT)") (class "Default")
      (node (ref "IC1") (pin "7") (pinfunction "OUT_7") (pintype "output"))
      (node (ref "R308") (pin "1") (pinfunction "1_1") (pintype "passive"))
      (node (ref "R310") (pin "2") (pinfunction "2_2") (pintype "passive"))
    )
    (net (code "49") (name "Net-(IC1C--IN)") (class "Default")
      (node (ref "IC1") (pin "9") (pinfunction "-IN_9") (pintype "input"))
      (node (ref "R301") (pin "1") (pinfunction "1_1") (pintype "passive"))
      (node (ref "R303") (pin "2") (pinfunction "2_2") (pintype "passive"))
    )
    (net (code "50") (name "Net-(IC1C-OUT)") (class "Default")
      (node (ref "IC1") (pin "8") (pinfunction "OUT_8") (pintype "output"))
      (node (ref "R303") (pin "1") (pinfunction "1_1") (pintype "passive"))
      (node (ref "R305") (pin "2") (pinfunction "2_2") (pintype "passive"))
    )
    (net (code "51") (name "Net-(IC1D--IN)") (class "Default")
      (node (ref "IC1") (pin "13") (pinfunction "-IN_13") (pintype "input"))
      (node (ref "R305") (pin "1") (pinfunction "1_1") (pintype "passive"))
      (node (ref "R307") (pin "1") (pinfunction "1_1") (pintype "passive"))
      (node (ref "R309") (pin "2") (pinfunction "2_2") (pintype "passive"))
    )
    (net (code "52") (name "Net-(IC1D-OUT)") (class "Default")
      (node (ref "IC1") (pin "14") (pinfunction "OUT_14") (pintype "output"))
      (node (ref "R309") (pin "1") (pinfunction "1_1") (pintype "passive"))
      (node (ref "R311") (pin "2") (pinfunction "2_2") (pintype "passive"))
    )
    (net (code "53") (name "Net-(IC2A--IN)") (class "Default")
      (node (ref "IC2") (pin "2") (pinfunction "-IN_2") (pintype "input"))
      (node (ref "R500") (pin "2") (pinfunction "2_2") (pintype "passive"))
      (node (ref "R501") (pin "2") (pinfunction "2_2") (pintype "passive"))
      (node (ref "R502") (pin "2") (pinfunction "2_2") (pintype "passive"))
      (node (ref "R503") (pin "1") (pinfunction "1_1") (pintype "passive"))
    )
    (net (code "54") (name "Net-(IC2A-OUT)") (class "Default")
      (node (ref "IC2") (pin "1") (pinfunction "OUT_1") (pintype "output"))
      (node (ref "R503") (pin "2") (pinfunction "2_2") (pintype "passive"))
      (node (ref "R504") (pin "2") (pinfunction "2_2") (pintype "passive"))
    )
    (net (code "55") (name "Net-(IC2B--IN)") (class "Default")
      (node (ref "IC2") (pin "6") (pinfunction "-IN_6") (pintype "input"))
      (node (ref "R600") (pin "2") (pinfunction "2_2") (pintype "passive"))
      (node (ref "R601") (pin "2") (pinfunction "2_2") (pintype "passive"))
      (node (ref "R602") (pin "2") (pinfunction "2_2") (pintype "passive"))
      (node (ref "R603") (pin "1") (pinfunction "1_1") (pintype "passive"))
    )
    (net (code "56") (name "Net-(IC2B-OUT)") (class "Default")
      (node (ref "IC2") (pin "7") (pinfunction "OUT_7") (pintype "output"))
      (node (ref "R603") (pin "2") (pinfunction "2_2") (pintype "passive"))
      (node (ref "R604") (pin "2") (pinfunction "2_2") (pintype "passive"))
    )
    (net (code "57") (name "Net-(IC2C--IN)") (class "Default")
      (node (ref "IC2") (pin "9") (pinfunction "-IN_9") (pintype "input"))
      (node (ref "R700") (pin "2") (pinfunction "2_2") (pintype "passive"))
      (node (ref "R701") (pin "2") (pinfunction "2_2") (pintype "passive"))
      (node (ref "R702") (pin "2") (pinfunction "2_2") (pintype "passive"))
      (node (ref "R703") (pin "1") (pinfunction "1_1") (pintype "passive"))
    )
    (net (code "58") (name "Net-(IC2C-OUT)") (class "Default")
      (node (ref "IC2") (pin "8") (pinfunction "OUT_8") (pintype "output"))
      (node (ref "R703") (pin "2") (pinfunction "2_2") (pintype "passive"))
      (node (ref "R704") (pin "2") (pinfunction "2_2") (pintype "passive"))
    )
    (net (code "59") (name "Net-(IC2D--IN)") (class "Default")
      (node (ref "IC2") (pin "13") (pinfunction "-IN_13") (pintype "input"))
      (node (ref "R800") (pin "2") (pinfunction "2_2") (pintype "passive"))
      (node (ref "R801") (pin "2") (pinfunction "2_2") (pintype "passive"))
      (node (ref "R802") (pin "2") (pinfunction "2_2") (pintype "passive"))
      (node (ref "R803") (pin "1") (pinfunction "1_1") (pintype "passive"))
    )
    (net (code "60") (name "Net-(IC2D-OUT)") (class "Default")
      (node (ref "IC2") (pin "14") (pinfunction "OUT_14") (pintype "output"))
      (node (ref "R803") (pin "2") (pinfunction "2_2") (pintype "passive"))
      (node (ref "R804") (pin "2") (pinfunction "2_2") (pintype "passive"))
    )
    (net (code "61") (name "Net-(IC3A--IN)") (class "Default")
      (node (ref "IC3") (pin "2") (pinfunction "-IN_2") (pintype "input"))
      (node (ref "R400") (pin "2") (pinfunction "2_2") (pintype "passive"))
      (node (ref "R402") (pin "2") (pinfunction "2_2") (pintype "passive"))
      (node (ref "R404") (pin "1") (pinfunction "1_1") (pintype "passive"))
    )
    (net (code "62") (name "Net-(IC3A-OUT)") (class "Default")
      (node (ref "IC3") (pin "1") (pinfunction "OUT_1") (pintype "output"))
      (node (ref "R404") (pin "2") (pinfunction "2_2") (pintype "passive"))
      (node (ref "R406") (pin "1") (pinfunction "1_1") (pintype "passive"))
    )
    (net (code "63") (name "Net-(IC3B--IN)") (class "Default")
      (node (ref "IC3") (pin "6") (pinfunction "-IN_6") (pintype "input"))
      (node (ref "R401") (pin "2") (pinfunction "2_2") (pintype "passive"))
      (node (ref "R403") (pin "2") (pinfunction "2_2") (pintype "passive"))
      (node (ref "R405") (pin "1") (pinfunction "1_1") (pintype "passive"))
    )
    (net (code "64") (name "Net-(IC3B-OUT)") (class "Default")
      (node (ref "IC3") (pin "7") (pinfunction "OUT_7") (pintype "output"))
      (node (ref "R405") (pin "2") (pinfunction "2_2") (pintype "passive"))
      (node (ref "R407") (pin "1") (pinfunction "1_1") (pintype "passive"))
    )
    (net (code "65") (name "Net-(IN_D-3)") (class "Default")
      (node (ref "IN_D") (pin "P$3") (pinfunction "3_P$3") (pintype "passive"))
      (node (ref "R904") (pin "1") (pinfunction "1_1") (pintype "passive"))
    )
    (net (code "66") (name "Net-(OUT_D-3)") (class "Default")
      (node (ref "OUT_D") (pin "P$3") (pinfunction "3_P$3") (pintype "passive"))
      (node (ref "R902") (pin "1") (pinfunction "1_1") (pintype "passive"))
      (node (ref "R903") (pin "2") (pinfunction "2_2") (pintype "passive"))
    )
    (net (code "67") (name "Net-(POT1-Pad2)") (class "Default")
      (node (ref "POT1") (pin "2") (pinfunction "2_2") (pintype "bidirectional"))
      (node (ref "R501") (pin "1") (pinfunction "1_1") (pintype "passive"))
    )
    (net (code "68") (name "Net-(POT2-Pad2)") (class "Default")
      (node (ref "POT2") (pin "2") (pinfunction "2_2") (pintype "bidirectional"))
      (node (ref "R601") (pin "1") (pinfunction "1_1") (pintype "passive"))
    )
    (net (code "69") (name "Net-(POT3-Pad2)") (class "Default")
      (node (ref "POT3") (pin "2") (pinfunction "2_2") (pintype "bidirectional"))
      (node (ref "R701") (pin "1") (pinfunction "1_1") (pintype "passive"))
    )
    (net (code "70") (name "Net-(POT4-Pad2)") (class "Default")
      (node (ref "POT4") (pin "2") (pinfunction "2_2") (pintype "bidirectional"))
      (node (ref "R801") (pin "1") (pinfunction "1_1") (pintype "passive"))
    )
    (net (code "71") (name "Net-(POT5-Pad2)") (class "Default")
      (node (ref "POT5") (pin "2") (pinfunction "2_2") (pintype "bidirectional"))
      (node (ref "R500") (pin "1") (pinfunction "1_1") (pintype "passive"))
    )
    (net (code "72") (name "Net-(POT6-Pad2)") (class "Default")
      (node (ref "POT6") (pin "2") (pinfunction "2_2") (pintype "bidirectional"))
      (node (ref "R600") (pin "1") (pinfunction "1_1") (pintype "passive"))
    )
    (net (code "73") (name "Net-(POT7-Pad2)") (class "Default")
      (node (ref "POT7") (pin "2") (pinfunction "2_2") (pintype "bidirectional"))
      (node (ref "R700") (pin "1") (pinfunction "1_1") (pintype "passive"))
    )
    (net (code "74") (name "Net-(POT8-Pad2)") (class "Default")
      (node (ref "POT8") (pin "2") (pinfunction "2_2") (pintype "bidirectional"))
      (node (ref "R800") (pin "1") (pinfunction "1_1") (pintype "passive"))
    )
    (net (code "75") (name "Net-(Q900-B)") (class "Default")
      (node (ref "Q900") (pin "1") (pinfunction "B_1") (pintype "passive"))
      (node (ref "R900") (pin "2") (pinfunction "2_2") (pintype "passive"))
    )
    (net (code "76") (name "Net-(Q900-C)") (class "Default")
      (node (ref "Q900") (pin "3") (pinfunction "C_3") (pintype "passive"))
      (node (ref "R901") (pin "1") (pinfunction "1_1") (pintype "passive"))
      (node (ref "R902") (pin "2") (pinfunction "2_2") (pintype "passive"))
    )
    (net (code "77") (name "Net-(Q901-B)") (class "Default")
      (node (ref "Q901") (pin "1") (pinfunction "B_1") (pintype "passive"))
      (node (ref "R904") (pin "2") (pinfunction "2_2") (pintype "passive"))
      (node (ref "R905") (pin "2") (pinfunction "2_2") (pintype "passive"))
    )
    (net (code "78") (name "Net-(R101-Pad2)") (class "Default")
      (node (ref "R101") (pin "2") (pinfunction "2_2") (pintype "passive"))
      (node (ref "X1") (pin "D+") (pinfunction "D+_D+") (pintype "bidirectional"))
    )
    (net (code "79") (name "Net-(R102-Pad2)") (class "Default")
      (node (ref "R102") (pin "2") (pinfunction "2_2") (pintype "passive"))
      (node (ref "X1") (pin "D-") (pinfunction "D-_D-") (pintype "bidirectional"))
    )
    (net (code "80") (name "Net-(R103-Pad2)") (class "Default")
      (node (ref "R103") (pin "2") (pinfunction "2_2") (pintype "passive"))
      (node (ref "X1") (pin "VBUS") (pinfunction "VBUS_VBUS") (pintype "bidirectional"))
    )
    (net (code "81") (name "Net-(U$1-LED_R+)") (class "Default")
      (node (ref "R100") (pin "1") (pinfunction "1_1") (pintype "passive"))
      (node (ref "U$1") (pin "+3") (pinfunction "LED_R+_+3") (pintype "input"))
    )
    (net (code "82") (name "VCC{slash}2") (class "Default")
      (node (ref "VMID") (pin "1") (pinfunction "1_1") (pintype "passive"))
    )
    (net (code "83") (name "unconnected-(OUT_D-4-PadP$2)") (class "Default")
      (node (ref "OUT_D") (pin "P$2") (pinfunction "4_P$2") (pintype "passive"))
    )
    (net (code "84") (name "unconnected-(OUT_L-4-PadP$2)") (class "Default")
      (node (ref "OUT_L") (pin "P$2") (pinfunction "4_P$2") (pintype "passive"))
    )
    (net (code "85") (name "unconnected-(OUT_R-4-PadP$2)") (class "Default")
      (node (ref "OUT_R") (pin "P$2") (pinfunction "4_P$2") (pintype "passive"))
    )
    (net (code "86") (name "unconnected-(U$2-Pad13)") (class "Default")
      (node (ref "U$2") (pin "13") (pinfunction "13_13") (pintype "passive"))
    )
    (net (code "87") (name "unconnected-(U$2-Pad14)") (class "Default")
      (node (ref "U$2") (pin "14") (pinfunction "14_14") (pintype "passive"))
    )
    (net (code "88") (name "unconnected-(U$2-Pad15)") (class "Default")
      (node (ref "U$2") (pin "15") (pinfunction "15_15") (pintype "passive"))
    )
    (net (code "89") (name "unconnected-(U$2-Pad16)") (class "Default")
      (node (ref "U$2") (pin "16") (pinfunction "16_16") (pintype "passive"))
    )
  )
)
